# Flashing_2_LEDS.net
KiCad netlist of a schematic drawn in EAGLE
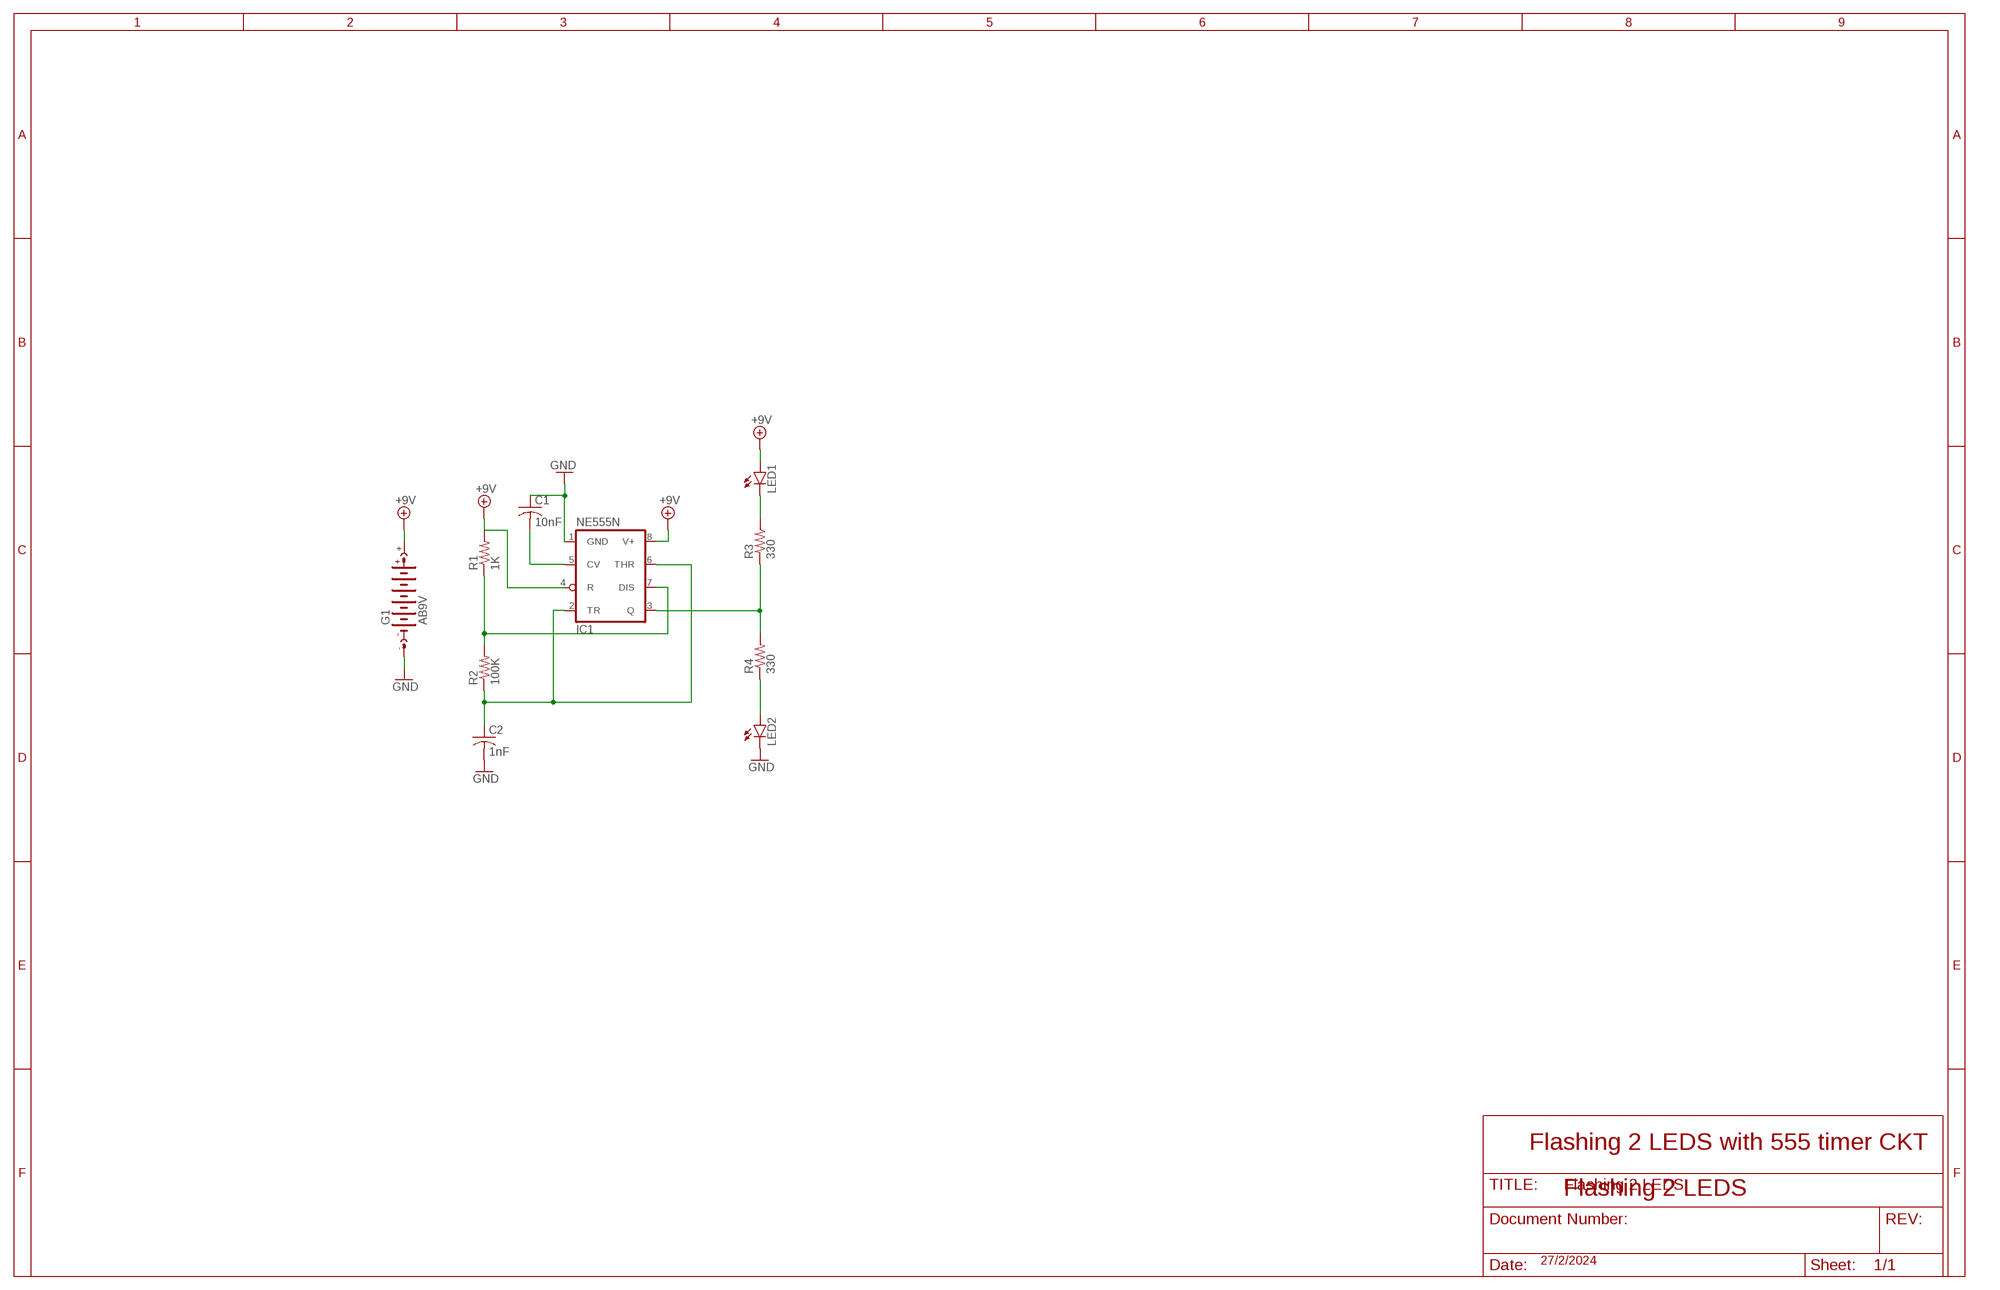
[diagram p0: schematic, sheet 1]

(export (version "E")
  (design (tool "Eeschema 10.0.6"))
  (components
    (comp (ref "C1")
      (value "10nF")
      (footprint "eagle-import:C1206")
      (libsource (lib "eagle-import") (part "C-USC1206"))
    )
    (comp (ref "C2")
      (value "1nF")
      (footprint "eagle-import:C1206")
      (libsource (lib "eagle-import") (part "C-USC1206"))
    )
    (comp (ref "G1")
      (value "AB9V")
      (footprint "eagle-import:AB9V")
      (libsource (lib "eagle-import") (part "AB9V"))
    )
    (comp (ref "IC1")
      (value "NE555N")
      (footprint "eagle-import:DIL08")
      (libsource (lib "eagle-import") (part "555NNE"))
    )
    (comp (ref "LED1")
      (value "LED5MM")
      (footprint "eagle-import:LED5MM")
      (libsource (lib "eagle-import") (part "LED5MM"))
    )
    (comp (ref "LED2")
      (value "LED5MM")
      (footprint "eagle-import:LED5MM")
      (libsource (lib "eagle-import") (part "LED5MM"))
    )
    (comp (ref "R1")
      (value "1K")
      (footprint "eagle-import:R0603")
      (libsource (lib "eagle-import") (part "R-US_R0603"))
    )
    (comp (ref "R2")
      (value "100K")
      (footprint "eagle-import:R0603")
      (libsource (lib "eagle-import") (part "R-US_R0603"))
    )
    (comp (ref "R3")
      (value "330")
      (footprint "eagle-import:R0603")
      (libsource (lib "eagle-import") (part "R-US_R0603"))
    )
    (comp (ref "R4")
      (value "330")
      (footprint "eagle-import:R0603")
      (libsource (lib "eagle-import") (part "R-US_R0603"))
    )
  )
  (nets
    (net (code "1") (name "+9V") (class "Default")
      (node (ref "G1") (pin "+") (pinfunction "+_+") (pintype "passive"))
      (node (ref "IC1") (pin "4") (pinfunction "R_4") (pintype "input"))
      (node (ref "IC1") (pin "8") (pinfunction "V+_8") (pintype "power_in"))
      (node (ref "LED1") (pin "A") (pinfunction "A_A") (pintype "passive"))
      (node (ref "R1") (pin "2") (pinfunction "2_2") (pintype "passive"))
    )
    (net (code "2") (name "GND") (class "Default")
      (node (ref "C1") (pin "1") (pinfunction "1_1") (pintype "passive"))
      (node (ref "C2") (pin "2") (pinfunction "2_2") (pintype "passive"))
      (node (ref "G1") (pin "-") (pinfunction "-_-") (pintype "passive"))
      (node (ref "IC1") (pin "1") (pinfunction "GND_1") (pintype "power_in"))
      (node (ref "LED2") (pin "K") (pinfunction "C_K") (pintype "passive"))
    )
    (net (code "3") (name "Net-(IC1-CV)") (class "Default")
      (node (ref "C1") (pin "2") (pinfunction "2_2") (pintype "passive"))
      (node (ref "IC1") (pin "5") (pinfunction "CV_5") (pintype "input"))
    )
    (net (code "4") (name "Net-(IC1-DIS)") (class "Default")
      (node (ref "IC1") (pin "7") (pinfunction "DIS_7") (pintype "input"))
      (node (ref "R1") (pin "1") (pinfunction "1_1") (pintype "passive"))
      (node (ref "R2") (pin "2") (pinfunction "2_2") (pintype "passive"))
    )
    (net (code "5") (name "Net-(IC1-Q)") (class "Default")
      (node (ref "IC1") (pin "3") (pinfunction "Q_3") (pintype "output"))
      (node (ref "R3") (pin "1") (pinfunction "1_1") (pintype "passive"))
      (node (ref "R4") (pin "2") (pinfunction "2_2") (pintype "passive"))
    )
    (net (code "6") (name "Net-(IC1-THR)") (class "Default")
      (node (ref "C2") (pin "1") (pinfunction "1_1") (pintype "passive"))
      (node (ref "IC1") (pin "2") (pinfunction "TR_2") (pintype "input"))
      (node (ref "IC1") (pin "6") (pinfunction "THR_6") (pintype "input"))
      (node (ref "R2") (pin "1") (pinfunction "1_1") (pintype "passive"))
    )
    (net (code "7") (name "Net-(LED1-C)") (class "Default")
      (node (ref "LED1") (pin "K") (pinfunction "C_K") (pintype "passive"))
      (node (ref "R3") (pin "2") (pinfunction "2_2") (pintype "passive"))
    )
    (net (code "8") (name "Net-(LED2-PadA)") (class "Default")
      (node (ref "LED2") (pin "A") (pinfunction "A_A") (pintype "passive"))
      (node (ref "R4") (pin "1") (pinfunction "1_1") (pintype "passive"))
    )
  )
)
